# prize_delivery.net
KiCad netlist of a schematic drawn in EAGLE
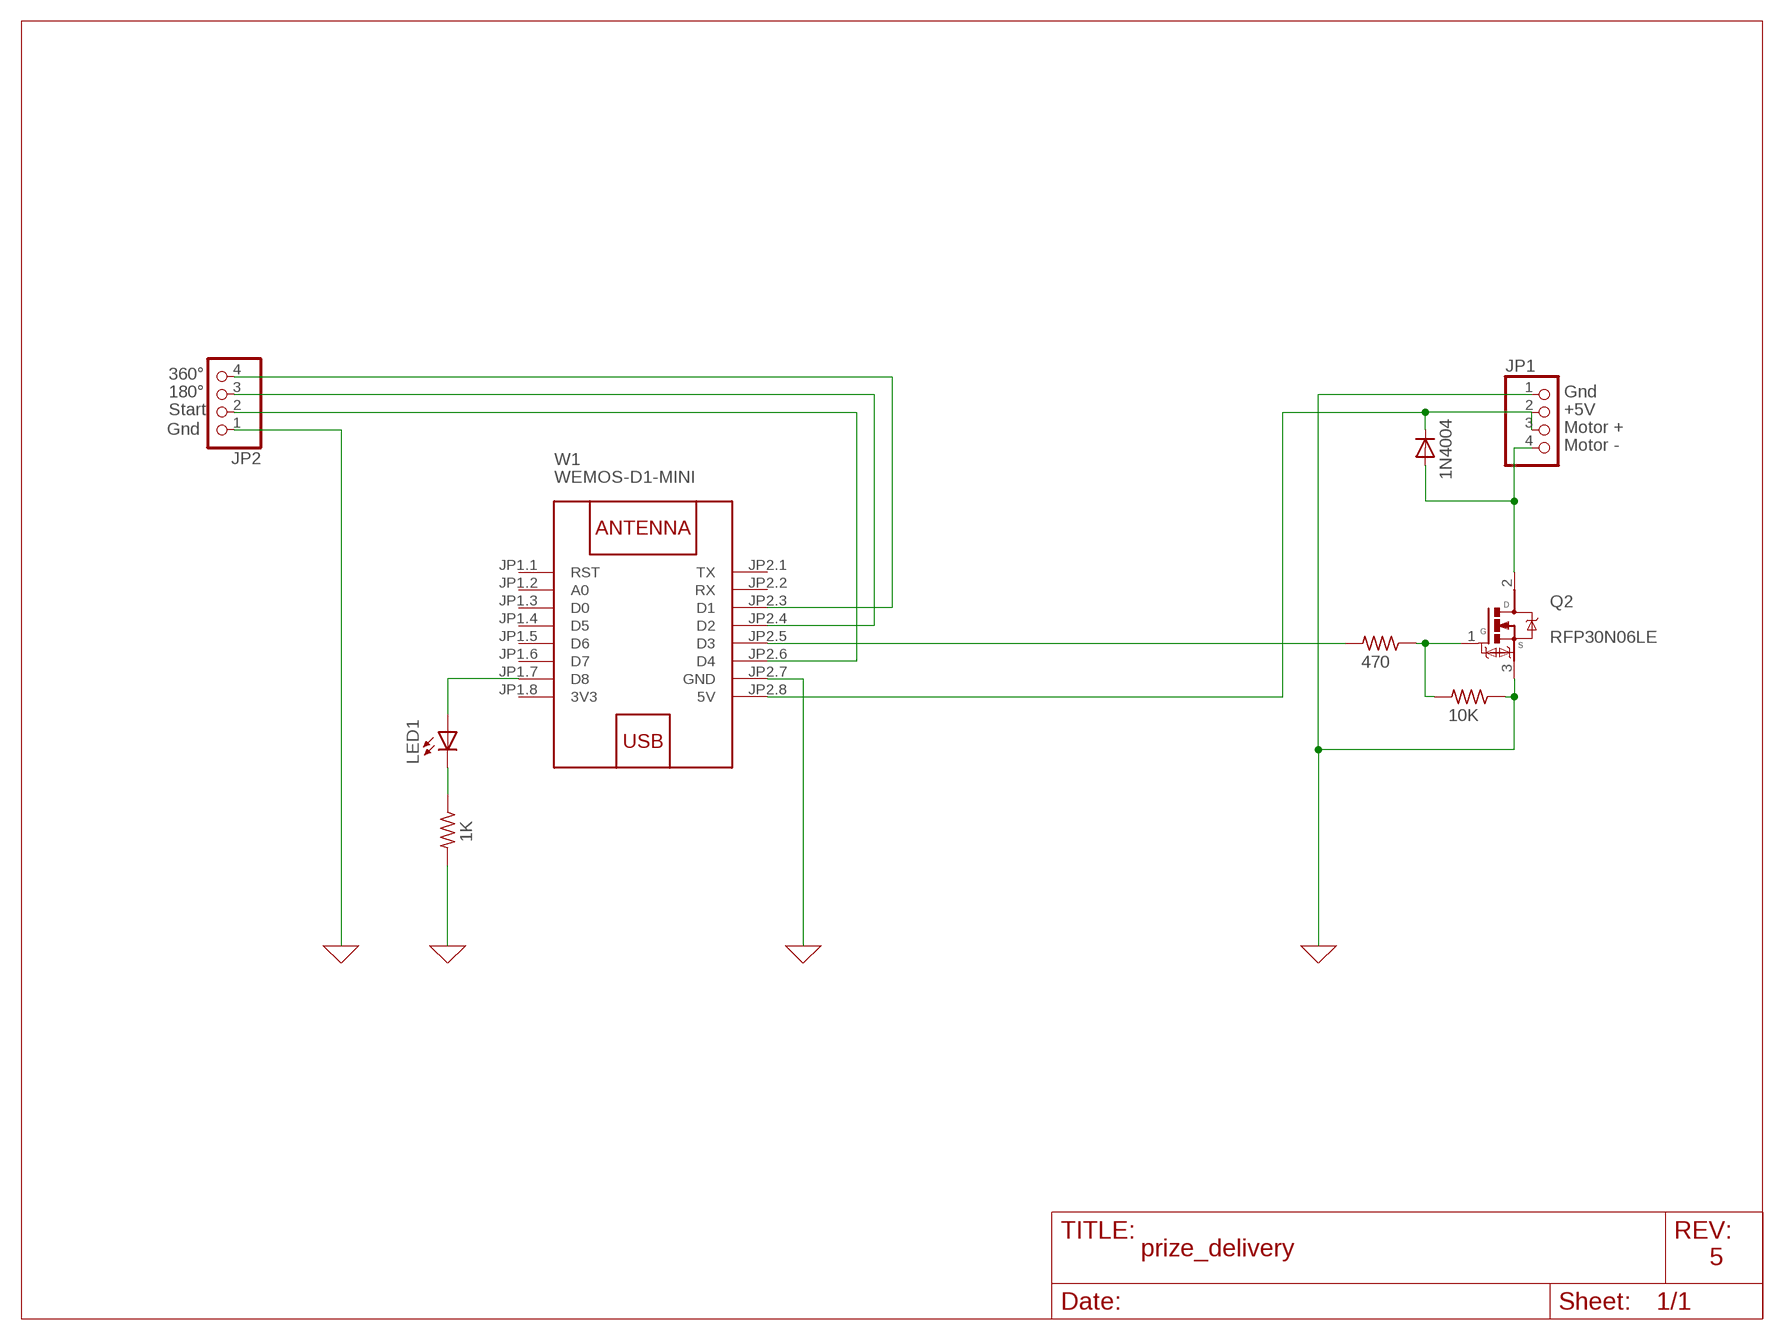
[diagram p0: schematic, sheet 1]

(export (version "E")
  (design (tool "Eeschema 10.0.6"))
  (components
    (comp (ref "D1")
      (value "1N4004")
      (footprint "eagle-import:DO41-10")
      (libsource (lib "eagle-import") (part "1N4004"))
    )
    (comp (ref "JP1")
      (value "PINHD-1X4")
      (footprint "eagle-import:1X04")
      (libsource (lib "eagle-import") (part "PINHD-1X4"))
    )
    (comp (ref "JP2")
      (value "PINHD-1X4")
      (footprint "eagle-import:1X04")
      (libsource (lib "eagle-import") (part "PINHD-1X4"))
    )
    (comp (ref "LED1")
      (value "LED5MM")
      (footprint "eagle-import:LED5MM")
      (libsource (lib "eagle-import") (part "LED5MM"))
    )
    (comp (ref "Q2")
      (value "RFP30N06LE")
      (footprint "eagle-import:TRANS_RFP30N06LE")
      (fields (field (name "MF") "ON Semiconductor"))
      (libsource (lib "eagle-import") (part "RFP30N06LE"))
    )
    (comp (ref "R1")
      (value "1K")
      (footprint "eagle-import:0207_10")
      (libsource (lib "eagle-import") (part "R-US_0207/10"))
    )
    (comp (ref "R2")
      (value "470")
      (footprint "eagle-import:0207_10")
      (libsource (lib "eagle-import") (part "R-US_0207/10"))
    )
    (comp (ref "R4")
      (value "10K")
      (footprint "eagle-import:0207_10")
      (libsource (lib "eagle-import") (part "R-US_0207/10"))
    )
    (comp (ref "W1")
      (value "WEMOS-D1-MINI")
      (footprint "eagle-import:WEMOS-D1-MINI")
      (libsource (lib "eagle-import") (part "WEMOS-D1-MINI"))
    )
  )
  (nets
    (net (code "1") (name "/3V3") (class "Default")
      (node (ref "W1") (pin "JP1.8") (pinfunction "3V3_JP1.8") (pintype "power_in"))
    )
    (net (code "2") (name "GND") (class "Default")
      (node (ref "JP1") (pin "1") (pinfunction "1_1") (pintype "passive"))
      (node (ref "JP2") (pin "1") (pinfunction "1_1") (pintype "passive"))
      (node (ref "Q2") (pin "3") (pinfunction "S_3") (pintype "power_in"))
      (node (ref "R1") (pin "2") (pinfunction "2_2") (pintype "passive"))
      (node (ref "R4") (pin "1") (pinfunction "1_1") (pintype "passive"))
      (node (ref "W1") (pin "JP2.7") (pinfunction "GND_JP2.7") (pintype "power_in"))
    )
    (net (code "3") (name "Net-(LED1-C)") (class "Default")
      (node (ref "LED1") (pin "K") (pinfunction "C_K") (pintype "passive"))
      (node (ref "R1") (pin "1") (pinfunction "1_1") (pintype "passive"))
    )
    (net (code "4") (name "Net-(Q2-D)") (class "Default")
      (node (ref "D1") (pin "A") (pinfunction "A_A") (pintype "passive"))
      (node (ref "JP1") (pin "4") (pinfunction "4_4") (pintype "passive"))
      (node (ref "Q2") (pin "2") (pinfunction "D_2") (pintype "power_in"))
    )
    (net (code "5") (name "Net-(Q2-G)") (class "Default")
      (node (ref "Q2") (pin "1") (pinfunction "G_1") (pintype "input"))
      (node (ref "R2") (pin "1") (pinfunction "1_1") (pintype "passive"))
      (node (ref "R4") (pin "2") (pinfunction "2_2") (pintype "passive"))
    )
    (net (code "6") (name "Net-(W1-5V)") (class "Default")
      (node (ref "D1") (pin "C") (pinfunction "C_C") (pintype "passive"))
      (node (ref "JP1") (pin "2") (pinfunction "2_2") (pintype "passive"))
      (node (ref "JP1") (pin "3") (pinfunction "3_3") (pintype "passive"))
      (node (ref "W1") (pin "JP2.8") (pinfunction "5V_JP2.8") (pintype "power_in"))
    )
    (net (code "7") (name "Net-(W1-D1)") (class "Default")
      (node (ref "JP2") (pin "4") (pinfunction "4_4") (pintype "passive"))
      (node (ref "W1") (pin "JP2.3") (pinfunction "D1_JP2.3") (pintype "bidirectional"))
    )
    (net (code "8") (name "Net-(W1-D2)") (class "Default")
      (node (ref "JP2") (pin "3") (pinfunction "3_3") (pintype "passive"))
      (node (ref "W1") (pin "JP2.4") (pinfunction "D2_JP2.4") (pintype "bidirectional"))
    )
    (net (code "9") (name "Net-(W1-D3)") (class "Default")
      (node (ref "R2") (pin "2") (pinfunction "2_2") (pintype "passive"))
      (node (ref "W1") (pin "JP2.5") (pinfunction "D3_JP2.5") (pintype "bidirectional"))
    )
    (net (code "10") (name "Net-(W1-D4)") (class "Default")
      (node (ref "JP2") (pin "2") (pinfunction "2_2") (pintype "passive"))
      (node (ref "W1") (pin "JP2.6") (pinfunction "D4_JP2.6") (pintype "bidirectional"))
    )
    (net (code "11") (name "Net-(W1-D8)") (class "Default")
      (node (ref "LED1") (pin "A") (pinfunction "A_A") (pintype "passive"))
      (node (ref "W1") (pin "JP1.7") (pinfunction "D8_JP1.7") (pintype "bidirectional"))
    )
    (net (code "12") (name "unconnected-(W1-A0-PadJP1.2)") (class "Default")
      (node (ref "W1") (pin "JP1.2") (pinfunction "A0_JP1.2") (pintype "bidirectional"))
    )
    (net (code "13") (name "unconnected-(W1-D0-PadJP1.3)") (class "Default")
      (node (ref "W1") (pin "JP1.3") (pinfunction "D0_JP1.3") (pintype "bidirectional"))
    )
    (net (code "14") (name "unconnected-(W1-D5-PadJP1.4)") (class "Default")
      (node (ref "W1") (pin "JP1.4") (pinfunction "D5_JP1.4") (pintype "bidirectional"))
    )
    (net (code "15") (name "unconnected-(W1-D6-PadJP1.5)") (class "Default")
      (node (ref "W1") (pin "JP1.5") (pinfunction "D6_JP1.5") (pintype "bidirectional"))
    )
    (net (code "16") (name "unconnected-(W1-D7-PadJP1.6)") (class "Default")
      (node (ref "W1") (pin "JP1.6") (pinfunction "D7_JP1.6") (pintype "bidirectional"))
    )
    (net (code "17") (name "unconnected-(W1-RST-PadJP1.1)") (class "Default")
      (node (ref "W1") (pin "JP1.1") (pinfunction "RST_JP1.1") (pintype "bidirectional"))
    )
    (net (code "18") (name "unconnected-(W1-RX-PadJP2.2)") (class "Default")
      (node (ref "W1") (pin "JP2.2") (pinfunction "RX_JP2.2") (pintype "bidirectional"))
    )
    (net (code "19") (name "unconnected-(W1-TX-PadJP2.1)") (class "Default")
      (node (ref "W1") (pin "JP2.1") (pinfunction "TX_JP2.1") (pintype "bidirectional"))
    )
  )
)
